# time_circuits_controller.net
KiCad netlist of a schematic drawn in EAGLE
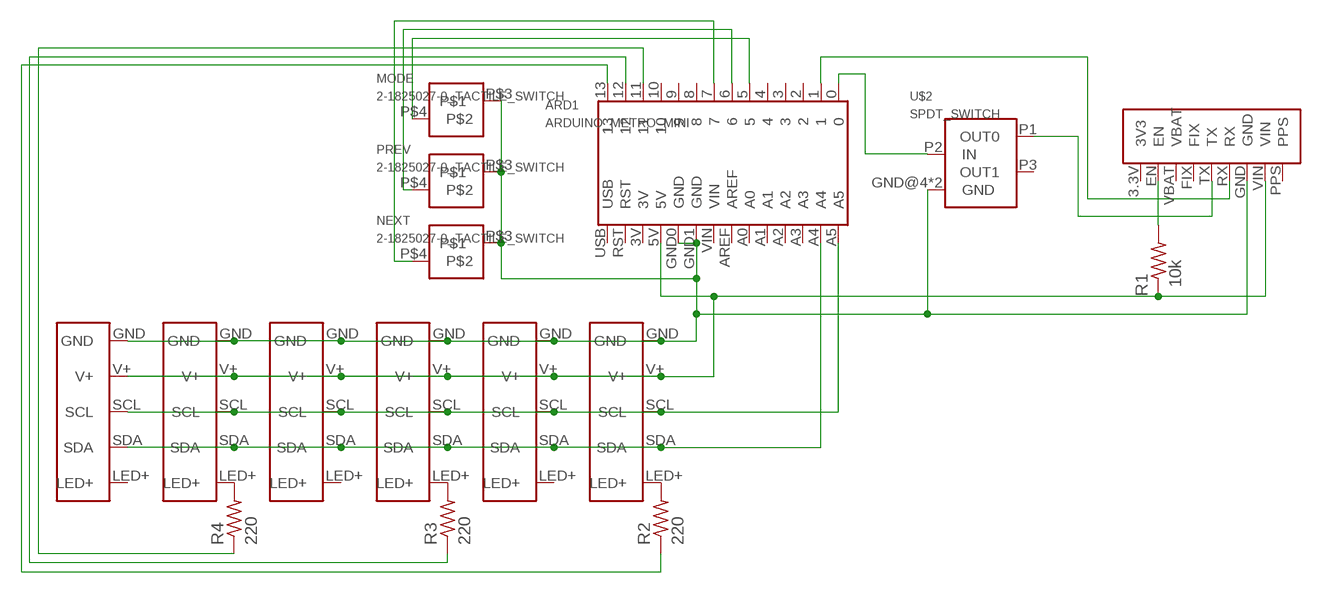
[diagram p0: schematic, sheet 1]

(export (version "E")
  (design (tool "Eeschema 10.0.6"))
  (components
    (comp (ref "ARD1")
      (value "ARDUINO_METRO_MINI")
      (footprint "eagle-import:ARDUINO_METRO_MINI")
      (libsource (lib "eagle-import") (part "ARDUINO_METRO_MINI"))
    )
    (comp (ref "MODE")
      (value "2-1825027-0_TACTILE_SWITCH")
      (footprint "eagle-import:2-1825027-0_TACTILE_SWITCH")
      (libsource (lib "eagle-import") (part "2-1825027-0_TACTILE_SWITCH"))
    )
    (comp (ref "NEXT")
      (value "2-1825027-0_TACTILE_SWITCH")
      (footprint "eagle-import:2-1825027-0_TACTILE_SWITCH")
      (libsource (lib "eagle-import") (part "2-1825027-0_TACTILE_SWITCH"))
    )
    (comp (ref "OUTPUT_00")
      (value "INTERCONNECTOR4")
      (footprint "eagle-import:INTERCONNECTOR4")
      (libsource (lib "eagle-import") (part "INTERCONNECTOR4"))
    )
    (comp (ref "OUTPUT_01")
      (value "INTERCONNECTOR4")
      (footprint "eagle-import:INTERCONNECTOR4")
      (libsource (lib "eagle-import") (part "INTERCONNECTOR4"))
    )
    (comp (ref "OUTPUT_10")
      (value "INTERCONNECTOR4")
      (footprint "eagle-import:INTERCONNECTOR4")
      (libsource (lib "eagle-import") (part "INTERCONNECTOR4"))
    )
    (comp (ref "OUTPUT_11")
      (value "INTERCONNECTOR4")
      (footprint "eagle-import:INTERCONNECTOR4")
      (libsource (lib "eagle-import") (part "INTERCONNECTOR4"))
    )
    (comp (ref "OUTPUT_20")
      (value "INTERCONNECTOR4")
      (footprint "eagle-import:INTERCONNECTOR4")
      (libsource (lib "eagle-import") (part "INTERCONNECTOR4"))
    )
    (comp (ref "OUTPUT_21")
      (value "INTERCONNECTOR4")
      (footprint "eagle-import:INTERCONNECTOR4")
      (libsource (lib "eagle-import") (part "INTERCONNECTOR4"))
    )
    (comp (ref "PREV")
      (value "2-1825027-0_TACTILE_SWITCH")
      (footprint "eagle-import:2-1825027-0_TACTILE_SWITCH")
      (libsource (lib "eagle-import") (part "2-1825027-0_TACTILE_SWITCH"))
    )
    (comp (ref "R1")
      (value "10k")
      (footprint "eagle-import:0204_7")
      (libsource (lib "eagle-import") (part "R-US_0204/7"))
    )
    (comp (ref "R2")
      (value "220")
      (footprint "eagle-import:0204_7")
      (libsource (lib "eagle-import") (part "R-US_0204/7"))
    )
    (comp (ref "R3")
      (value "220")
      (footprint "eagle-import:0204_7")
      (libsource (lib "eagle-import") (part "R-US_0204/7"))
    )
    (comp (ref "R4")
      (value "220")
      (footprint "eagle-import:0204_7")
      (libsource (lib "eagle-import") (part "R-US_0204/7"))
    )
    (comp (ref "U$1")
      (value "GPSBREAKOUTV3")
      (footprint "eagle-import:GPSBREAKOUTV3")
      (libsource (lib "eagle-import") (part "GPSBREAKOUTV3"))
    )
    (comp (ref "U$2")
      (value "SPDT_SWITCH")
      (footprint "eagle-import:SPDT_SWITCH")
      (libsource (lib "eagle-import") (part "SPDT_SWITCH"))
    )
  )
  (nets
    (net (code "1") (name "Net-(ARD1-Pad1)") (class "Default")
      (node (ref "ARD1") (pin "1") (pinfunction "1_1") (pintype "bidirectional"))
      (node (ref "U$1") (pin "RX") (pinfunction "RX_RX") (pintype "bidirectional"))
    )
    (net (code "2") (name "Net-(ARD1-Pad5V)") (class "Default")
      (node (ref "ARD1") (pin "5V") (pinfunction "5V_5V") (pintype "bidirectional"))
      (node (ref "OUTPUT_00") (pin "V+") (pinfunction "V+_V+") (pintype "bidirectional"))
      (node (ref "OUTPUT_01") (pin "V+") (pinfunction "V+_V+") (pintype "bidirectional"))
      (node (ref "OUTPUT_10") (pin "V+") (pinfunction "V+_V+") (pintype "bidirectional"))
      (node (ref "OUTPUT_11") (pin "V+") (pinfunction "V+_V+") (pintype "bidirectional"))
      (node (ref "OUTPUT_20") (pin "V+") (pinfunction "V+_V+") (pintype "bidirectional"))
      (node (ref "OUTPUT_21") (pin "V+") (pinfunction "V+_V+") (pintype "bidirectional"))
      (node (ref "R1") (pin "1") (pinfunction "1_1") (pintype "passive"))
      (node (ref "U$1") (pin "VIN") (pinfunction "VIN_VIN") (pintype "bidirectional"))
    )
    (net (code "3") (name "Net-(ARD1-Pad11)") (class "Default")
      (node (ref "ARD1") (pin "11") (pinfunction "11_11") (pintype "bidirectional"))
      (node (ref "R4") (pin "1") (pinfunction "1_1") (pintype "passive"))
    )
    (net (code "4") (name "Net-(ARD1-Pad12)") (class "Default")
      (node (ref "ARD1") (pin "12") (pinfunction "12_12") (pintype "bidirectional"))
      (node (ref "R3") (pin "1") (pinfunction "1_1") (pintype "passive"))
    )
    (net (code "5") (name "Net-(ARD1-Pad13)") (class "Default")
      (node (ref "ARD1") (pin "13") (pinfunction "13_13") (pintype "bidirectional"))
      (node (ref "R2") (pin "1") (pinfunction "1_1") (pintype "passive"))
    )
    (net (code "6") (name "Net-(ARD1-PadA4)") (class "Default")
      (node (ref "ARD1") (pin "A4") (pinfunction "A4_A4") (pintype "bidirectional"))
      (node (ref "OUTPUT_00") (pin "SDA") (pinfunction "SDA_SDA") (pintype "bidirectional"))
      (node (ref "OUTPUT_01") (pin "SDA") (pinfunction "SDA_SDA") (pintype "bidirectional"))
      (node (ref "OUTPUT_10") (pin "SDA") (pinfunction "SDA_SDA") (pintype "bidirectional"))
      (node (ref "OUTPUT_11") (pin "SDA") (pinfunction "SDA_SDA") (pintype "bidirectional"))
      (node (ref "OUTPUT_20") (pin "SDA") (pinfunction "SDA_SDA") (pintype "bidirectional"))
      (node (ref "OUTPUT_21") (pin "SDA") (pinfunction "SDA_SDA") (pintype "bidirectional"))
    )
    (net (code "7") (name "Net-(ARD1-PadA5)") (class "Default")
      (node (ref "ARD1") (pin "A5") (pinfunction "A5_A5") (pintype "bidirectional"))
      (node (ref "OUTPUT_00") (pin "SCL") (pinfunction "SCL_SCL") (pintype "bidirectional"))
      (node (ref "OUTPUT_01") (pin "SCL") (pinfunction "SCL_SCL") (pintype "bidirectional"))
      (node (ref "OUTPUT_10") (pin "SCL") (pinfunction "SCL_SCL") (pintype "bidirectional"))
      (node (ref "OUTPUT_11") (pin "SCL") (pinfunction "SCL_SCL") (pintype "bidirectional"))
      (node (ref "OUTPUT_20") (pin "SCL") (pinfunction "SCL_SCL") (pintype "bidirectional"))
      (node (ref "OUTPUT_21") (pin "SCL") (pinfunction "SCL_SCL") (pintype "bidirectional"))
    )
    (net (code "8") (name "Net-(MODE-P$1)") (class "Default")
      (node (ref "ARD1") (pin "GND0") (pinfunction "GND_GND0") (pintype "bidirectional"))
      (node (ref "ARD1") (pin "GND1") (pinfunction "GND_GND1") (pintype "bidirectional"))
      (node (ref "MODE") (pin "P$3") (pinfunction "P$1_P$3") (pintype "bidirectional"))
      (node (ref "NEXT") (pin "P$3") (pinfunction "P$1_P$3") (pintype "bidirectional"))
      (node (ref "OUTPUT_00") (pin "GND") (pinfunction "GND_GND") (pintype "bidirectional"))
      (node (ref "OUTPUT_01") (pin "GND") (pinfunction "GND_GND") (pintype "bidirectional"))
      (node (ref "OUTPUT_10") (pin "GND") (pinfunction "GND_GND") (pintype "bidirectional"))
      (node (ref "OUTPUT_11") (pin "GND") (pinfunction "GND_GND") (pintype "bidirectional"))
      (node (ref "OUTPUT_20") (pin "GND") (pinfunction "GND_GND") (pintype "bidirectional"))
      (node (ref "OUTPUT_21") (pin "GND") (pinfunction "GND_GND") (pintype "bidirectional"))
      (node (ref "PREV") (pin "P$3") (pinfunction "P$1_P$3") (pintype "bidirectional"))
      (node (ref "U$1") (pin "GND") (pinfunction "GND_GND") (pintype "bidirectional"))
      (node (ref "U$2") (pin "GND@4") (pinfunction "GND_GND@4") (pintype "bidirectional"))
      (node (ref "U$2") (pin "GND@5") (pinfunction "GND_GND@5") (pintype "bidirectional"))
    )
    (net (code "9") (name "Net-(MODE-P$2)") (class "Default")
      (node (ref "ARD1") (pin "5") (pinfunction "5_5") (pintype "bidirectional"))
      (node (ref "MODE") (pin "P$4") (pinfunction "P$2_P$4") (pintype "bidirectional"))
    )
    (net (code "10") (name "Net-(NEXT-P$2)") (class "Default")
      (node (ref "ARD1") (pin "7") (pinfunction "7_7") (pintype "bidirectional"))
      (node (ref "NEXT") (pin "P$4") (pinfunction "P$2_P$4") (pintype "bidirectional"))
    )
    (net (code "11") (name "Net-(OUTPUT_01-PadLED+)") (class "Default")
      (node (ref "OUTPUT_01") (pin "LED+") (pinfunction "LED+_LED+") (pintype "bidirectional"))
      (node (ref "R4") (pin "2") (pinfunction "2_2") (pintype "passive"))
    )
    (net (code "12") (name "Net-(OUTPUT_11-PadLED+)") (class "Default")
      (node (ref "OUTPUT_11") (pin "LED+") (pinfunction "LED+_LED+") (pintype "bidirectional"))
      (node (ref "R3") (pin "2") (pinfunction "2_2") (pintype "passive"))
    )
    (net (code "13") (name "Net-(OUTPUT_21-PadLED+)") (class "Default")
      (node (ref "OUTPUT_21") (pin "LED+") (pinfunction "LED+_LED+") (pintype "bidirectional"))
      (node (ref "R2") (pin "2") (pinfunction "2_2") (pintype "passive"))
    )
    (net (code "14") (name "Net-(PREV-P$2)") (class "Default")
      (node (ref "ARD1") (pin "6") (pinfunction "6_6") (pintype "bidirectional"))
      (node (ref "PREV") (pin "P$4") (pinfunction "P$2_P$4") (pintype "bidirectional"))
    )
    (net (code "15") (name "Net-(R1-Pad2)") (class "Default")
      (node (ref "R1") (pin "2") (pinfunction "2_2") (pintype "passive"))
      (node (ref "U$1") (pin "EN") (pinfunction "EN_EN") (pintype "bidirectional"))
    )
    (net (code "16") (name "Net-(U$2-IN)") (class "Default")
      (node (ref "ARD1") (pin "0") (pinfunction "0_0") (pintype "bidirectional"))
      (node (ref "U$2") (pin "P2") (pinfunction "IN_P2") (pintype "bidirectional"))
    )
    (net (code "17") (name "Net-(U$2-OUT0)") (class "Default")
      (node (ref "U$1") (pin "TX") (pinfunction "TX_TX") (pintype "bidirectional"))
      (node (ref "U$2") (pin "P1") (pinfunction "OUT0_P1") (pintype "bidirectional"))
    )
    (net (code "18") (name "unconnected-(ARD1-Pad2)") (class "Default")
      (node (ref "ARD1") (pin "2") (pinfunction "2_2") (pintype "bidirectional"))
    )
    (net (code "19") (name "unconnected-(ARD1-Pad3)") (class "Default")
      (node (ref "ARD1") (pin "3") (pinfunction "3_3") (pintype "bidirectional"))
    )
    (net (code "20") (name "unconnected-(ARD1-Pad3V)") (class "Default")
      (node (ref "ARD1") (pin "3V") (pinfunction "3V_3V") (pintype "bidirectional"))
    )
    (net (code "21") (name "unconnected-(ARD1-Pad4)") (class "Default")
      (node (ref "ARD1") (pin "4") (pinfunction "4_4") (pintype "bidirectional"))
    )
    (net (code "22") (name "unconnected-(ARD1-Pad8)") (class "Default")
      (node (ref "ARD1") (pin "8") (pinfunction "8_8") (pintype "bidirectional"))
    )
    (net (code "23") (name "unconnected-(ARD1-Pad9)") (class "Default")
      (node (ref "ARD1") (pin "9") (pinfunction "9_9") (pintype "bidirectional"))
    )
    (net (code "24") (name "unconnected-(ARD1-Pad10)") (class "Default")
      (node (ref "ARD1") (pin "10") (pinfunction "10_10") (pintype "bidirectional"))
    )
    (net (code "25") (name "unconnected-(ARD1-PadA0)") (class "Default")
      (node (ref "ARD1") (pin "A0") (pinfunction "A0_A0") (pintype "bidirectional"))
    )
    (net (code "26") (name "unconnected-(ARD1-PadA1)") (class "Default")
      (node (ref "ARD1") (pin "A1") (pinfunction "A1_A1") (pintype "bidirectional"))
    )
    (net (code "27") (name "unconnected-(ARD1-PadA2)") (class "Default")
      (node (ref "ARD1") (pin "A2") (pinfunction "A2_A2") (pintype "bidirectional"))
    )
    (net (code "28") (name "unconnected-(ARD1-PadA3)") (class "Default")
      (node (ref "ARD1") (pin "A3") (pinfunction "A3_A3") (pintype "bidirectional"))
    )
    (net (code "29") (name "unconnected-(ARD1-PadAREF)") (class "Default")
      (node (ref "ARD1") (pin "AREF") (pinfunction "AREF_AREF") (pintype "bidirectional"))
    )
    (net (code "30") (name "unconnected-(ARD1-PadRST)") (class "Default")
      (node (ref "ARD1") (pin "RST") (pinfunction "RST_RST") (pintype "bidirectional"))
    )
    (net (code "31") (name "unconnected-(ARD1-PadUSB)") (class "Default")
      (node (ref "ARD1") (pin "USB") (pinfunction "USB_USB") (pintype "bidirectional"))
    )
    (net (code "32") (name "unconnected-(ARD1-PadVIN)") (class "Default")
      (node (ref "ARD1") (pin "VIN") (pinfunction "VIN_VIN") (pintype "bidirectional"))
    )
    (net (code "33") (name "unconnected-(OUTPUT_00-PadLED+)") (class "Default")
      (node (ref "OUTPUT_00") (pin "LED+") (pinfunction "LED+_LED+") (pintype "bidirectional"))
    )
    (net (code "34") (name "unconnected-(OUTPUT_10-PadLED+)") (class "Default")
      (node (ref "OUTPUT_10") (pin "LED+") (pinfunction "LED+_LED+") (pintype "bidirectional"))
    )
    (net (code "35") (name "unconnected-(OUTPUT_20-PadLED+)") (class "Default")
      (node (ref "OUTPUT_20") (pin "LED+") (pinfunction "LED+_LED+") (pintype "bidirectional"))
    )
    (net (code "36") (name "unconnected-(U$1-3V3-Pad3.3V)") (class "Default")
      (node (ref "U$1") (pin "3.3V") (pinfunction "3V3_3.3V") (pintype "bidirectional"))
    )
    (net (code "37") (name "unconnected-(U$1-PadFIX)") (class "Default")
      (node (ref "U$1") (pin "FIX") (pinfunction "FIX_FIX") (pintype "bidirectional"))
    )
    (net (code "38") (name "unconnected-(U$1-PadPPS)") (class "Default")
      (node (ref "U$1") (pin "PPS") (pinfunction "PPS_PPS") (pintype "bidirectional"))
    )
    (net (code "39") (name "unconnected-(U$1-PadVBAT)") (class "Default")
      (node (ref "U$1") (pin "VBAT") (pinfunction "VBAT_VBAT") (pintype "bidirectional"))
    )
    (net (code "40") (name "unconnected-(U$2-OUT1-PadP3)") (class "Default")
      (node (ref "U$2") (pin "P3") (pinfunction "OUT1_P3") (pintype "bidirectional"))
    )
  )
)
